# Placa_PCB_Robot_CAOS.net
KiCad netlist of a schematic drawn in EAGLE
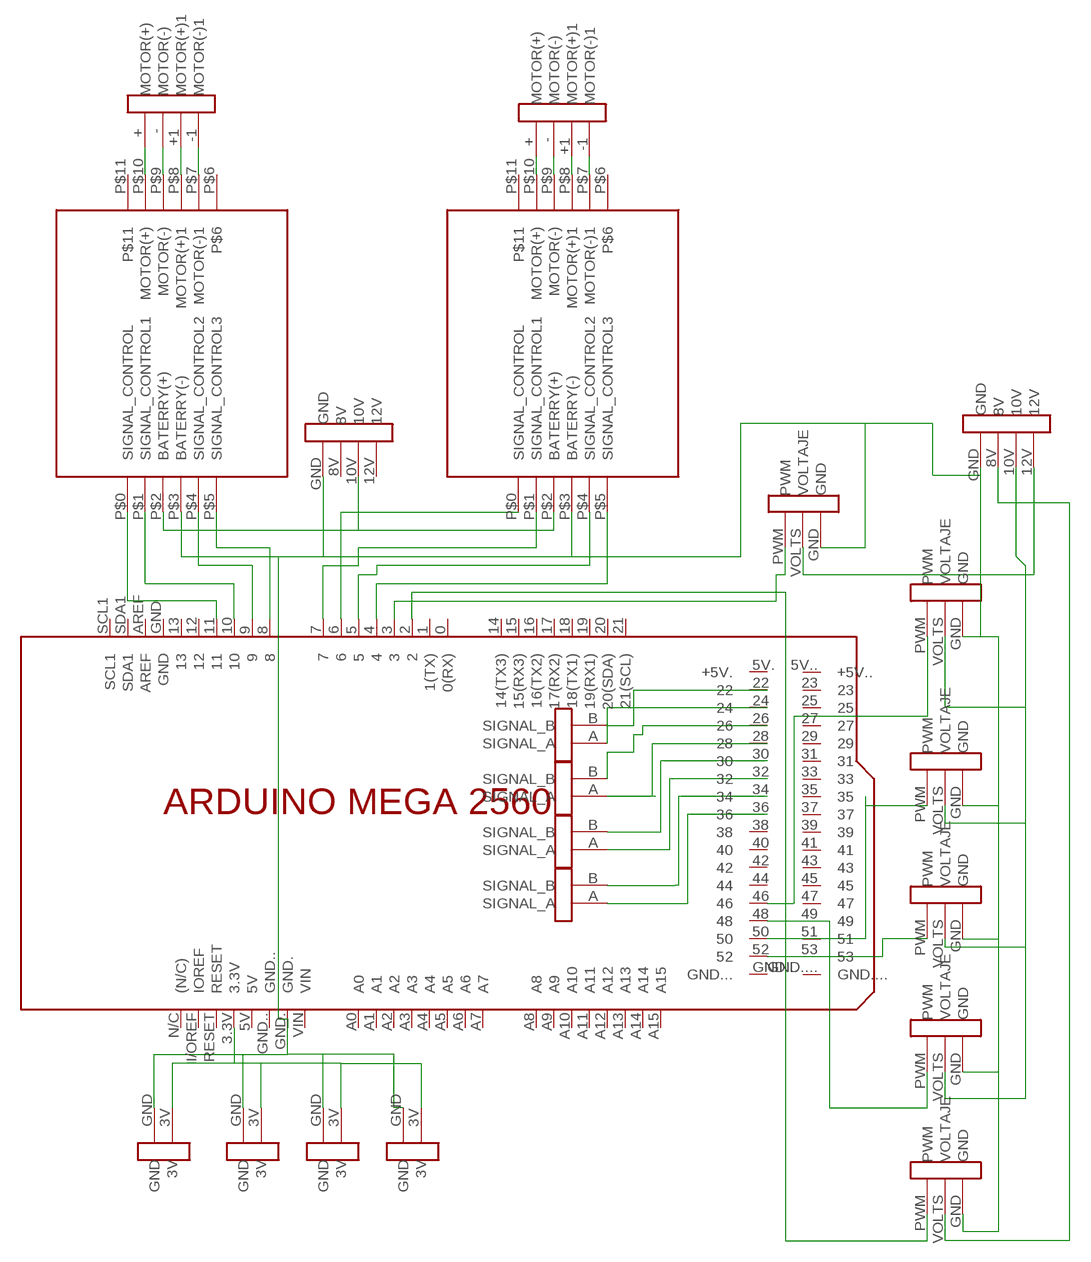
[diagram p0: schematic, sheet 1]

(export (version "E")
  (design (tool "Eeschema 10.0.6"))
  (components
    (comp (ref "INTENTO1")
      (value "DRV8833DRV8833")
      (footprint "eagle-import:DRV8833")
      (libsource (lib "eagle-import") (part "DRV8833DRV8833"))
    )
    (comp (ref "INTENTO2")
      (value "DRV8833DRV8833")
      (footprint "eagle-import:DRV8833")
      (libsource (lib "eagle-import") (part "DRV8833DRV8833"))
    )
    (comp (ref "PCB1")
      (value "ARDUINO_MEGA2560")
      (footprint "eagle-import:ARDUINO_MEGA2560")
      (libsource (lib "eagle-import") (part "ARDUINO_MEGA2560"))
    )
    (comp (ref "U$1")
      (value "MOTOR_CD")
      (footprint "eagle-import:MOTOR_CD")
      (libsource (lib "eagle-import") (part "MOTOR_CD"))
    )
    (comp (ref "U$2")
      (value "MOTOR_CD")
      (footprint "eagle-import:MOTOR_CD")
      (libsource (lib "eagle-import") (part "MOTOR_CD"))
    )
    (comp (ref "U$3")
      (value "BATTERY")
      (footprint "eagle-import:BATTERY")
      (libsource (lib "eagle-import") (part "BATTERY"))
    )
    (comp (ref "U$4")
      (value "SERVO_MOTORES")
      (footprint "eagle-import:SERVO_MOTOR")
      (libsource (lib "eagle-import") (part "SERVO_MOTORES"))
    )
    (comp (ref "U$5")
      (value "SERVO_MOTORES")
      (footprint "eagle-import:SERVO_MOTOR")
      (libsource (lib "eagle-import") (part "SERVO_MOTORES"))
    )
    (comp (ref "U$6")
      (value "SERVO_MOTORES")
      (footprint "eagle-import:SERVO_MOTOR")
      (libsource (lib "eagle-import") (part "SERVO_MOTORES"))
    )
    (comp (ref "U$7")
      (value "SERVO_MOTORES")
      (footprint "eagle-import:SERVO_MOTOR")
      (libsource (lib "eagle-import") (part "SERVO_MOTORES"))
    )
    (comp (ref "U$8")
      (value "SERVO_MOTORES")
      (footprint "eagle-import:SERVO_MOTOR")
      (libsource (lib "eagle-import") (part "SERVO_MOTORES"))
    )
    (comp (ref "U$9")
      (value "SERVO_MOTORES")
      (footprint "eagle-import:SERVO_MOTOR")
      (libsource (lib "eagle-import") (part "SERVO_MOTORES"))
    )
    (comp (ref "U$10")
      (value "BATTERY")
      (footprint "eagle-import:BATTERY")
      (libsource (lib "eagle-import") (part "BATTERY"))
    )
    (comp (ref "U$11")
      (value "ENCODER_VOLTAJE")
      (footprint "eagle-import:ENCODER_VOLTAJE")
      (libsource (lib "eagle-import") (part "ENCODER_VOLTAJE"))
    )
    (comp (ref "U$12")
      (value "ENCODER_VOLTAJE")
      (footprint "eagle-import:ENCODER_VOLTAJE")
      (libsource (lib "eagle-import") (part "ENCODER_VOLTAJE"))
    )
    (comp (ref "U$13")
      (value "ENCODER_VOLTAJE")
      (footprint "eagle-import:ENCODER_VOLTAJE")
      (libsource (lib "eagle-import") (part "ENCODER_VOLTAJE"))
    )
    (comp (ref "U$14")
      (value "ENCODER_VOLTAJE")
      (footprint "eagle-import:ENCODER_VOLTAJE")
      (libsource (lib "eagle-import") (part "ENCODER_VOLTAJE"))
    )
    (comp (ref "U$15")
      (value "SIGNAL_ENCODER2")
      (footprint "eagle-import:SIGNAL_ENCODER")
      (libsource (lib "eagle-import") (part "SIGNAL_ENCODER2"))
    )
    (comp (ref "U$16")
      (value "SIGNAL_ENCODER2")
      (footprint "eagle-import:SIGNAL_ENCODER")
      (libsource (lib "eagle-import") (part "SIGNAL_ENCODER2"))
    )
    (comp (ref "U$17")
      (value "SIGNAL_ENCODER2")
      (footprint "eagle-import:SIGNAL_ENCODER")
      (libsource (lib "eagle-import") (part "SIGNAL_ENCODER2"))
    )
    (comp (ref "U$18")
      (value "SIGNAL_ENCODER2")
      (footprint "eagle-import:SIGNAL_ENCODER")
      (libsource (lib "eagle-import") (part "SIGNAL_ENCODER2"))
    )
  )
  (nets
    (net (code "1") (name "Net-(INTENTO1-BATERRY(+))") (class "Default")
      (node (ref "INTENTO1") (pin "P$2") (pinfunction "BATERRY(+)_P$2") (pintype "bidirectional"))
      (node (ref "INTENTO2") (pin "P$2") (pinfunction "BATERRY(+)_P$2") (pintype "bidirectional"))
      (node (ref "U$3") (pin "10V") (pinfunction "10V_10V") (pintype "bidirectional"))
    )
    (net (code "2") (name "Net-(INTENTO1-BATERRY(-))") (class "Default")
      (node (ref "INTENTO1") (pin "P$3") (pinfunction "BATERRY(-)_P$3") (pintype "bidirectional"))
      (node (ref "INTENTO2") (pin "P$3") (pinfunction "BATERRY(-)_P$3") (pintype "bidirectional"))
      (node (ref "PCB1") (pin "GND.") (pinfunction "GND._GND.") (pintype "bidirectional"))
      (node (ref "U$10") (pin "GND") (pinfunction "GND_GND") (pintype "bidirectional"))
      (node (ref "U$11") (pin "GND") (pinfunction "GND_GND") (pintype "bidirectional"))
      (node (ref "U$12") (pin "GND") (pinfunction "GND_GND") (pintype "bidirectional"))
      (node (ref "U$13") (pin "GND") (pinfunction "GND_GND") (pintype "bidirectional"))
      (node (ref "U$14") (pin "GND") (pinfunction "GND_GND") (pintype "bidirectional"))
      (node (ref "U$3") (pin "GND") (pinfunction "GND_GND") (pintype "bidirectional"))
      (node (ref "U$4") (pin "GND") (pinfunction "GND_GND") (pintype "bidirectional"))
      (node (ref "U$5") (pin "GND") (pinfunction "GND_GND") (pintype "bidirectional"))
      (node (ref "U$6") (pin "GND") (pinfunction "GND_GND") (pintype "bidirectional"))
      (node (ref "U$7") (pin "GND") (pinfunction "GND_GND") (pintype "bidirectional"))
      (node (ref "U$8") (pin "GND") (pinfunction "GND_GND") (pintype "bidirectional"))
      (node (ref "U$9") (pin "GND") (pinfunction "GND_GND") (pintype "bidirectional"))
    )
    (net (code "3") (name "Net-(INTENTO1-MOTOR(+))") (class "Default")
      (node (ref "INTENTO1") (pin "P$10") (pinfunction "MOTOR(+)_P$10") (pintype "bidirectional"))
      (node (ref "U$1") (pin "+") (pinfunction "MOTOR(+)_+") (pintype "bidirectional"))
    )
    (net (code "4") (name "Net-(INTENTO1-MOTOR(+)1)") (class "Default")
      (node (ref "INTENTO1") (pin "P$8") (pinfunction "MOTOR(+)1_P$8") (pintype "bidirectional"))
      (node (ref "U$1") (pin "+1") (pinfunction "MOTOR(+)1_+1") (pintype "bidirectional"))
    )
    (net (code "5") (name "Net-(INTENTO1-MOTOR(-))") (class "Default")
      (node (ref "INTENTO1") (pin "P$9") (pinfunction "MOTOR(-)_P$9") (pintype "bidirectional"))
      (node (ref "U$1") (pin "-") (pinfunction "MOTOR(-)_-") (pintype "bidirectional"))
    )
    (net (code "6") (name "Net-(INTENTO1-MOTOR(-)1)") (class "Default")
      (node (ref "INTENTO1") (pin "P$7") (pinfunction "MOTOR(-)1_P$7") (pintype "bidirectional"))
      (node (ref "U$1") (pin "-1") (pinfunction "MOTOR(-)1_-1") (pintype "bidirectional"))
    )
    (net (code "7") (name "Net-(INTENTO1-SIGNAL_CONTROL)") (class "Default")
      (node (ref "INTENTO1") (pin "P$0") (pinfunction "SIGNAL_CONTROL_P$0") (pintype "bidirectional"))
      (node (ref "PCB1") (pin "11") (pinfunction "11_11") (pintype "bidirectional"))
    )
    (net (code "8") (name "Net-(INTENTO1-SIGNAL_CONTROL1)") (class "Default")
      (node (ref "INTENTO1") (pin "P$1") (pinfunction "SIGNAL_CONTROL1_P$1") (pintype "bidirectional"))
      (node (ref "PCB1") (pin "10") (pinfunction "10_10") (pintype "bidirectional"))
    )
    (net (code "9") (name "Net-(INTENTO1-SIGNAL_CONTROL2)") (class "Default")
      (node (ref "INTENTO1") (pin "P$4") (pinfunction "SIGNAL_CONTROL2_P$4") (pintype "bidirectional"))
      (node (ref "PCB1") (pin "9") (pinfunction "9_9") (pintype "bidirectional"))
    )
    (net (code "10") (name "Net-(INTENTO1-SIGNAL_CONTROL3)") (class "Default")
      (node (ref "INTENTO1") (pin "P$5") (pinfunction "SIGNAL_CONTROL3_P$5") (pintype "bidirectional"))
      (node (ref "PCB1") (pin "8") (pinfunction "8_8") (pintype "bidirectional"))
    )
    (net (code "11") (name "Net-(INTENTO2-MOTOR(+))") (class "Default")
      (node (ref "INTENTO2") (pin "P$10") (pinfunction "MOTOR(+)_P$10") (pintype "bidirectional"))
      (node (ref "U$2") (pin "+") (pinfunction "MOTOR(+)_+") (pintype "bidirectional"))
    )
    (net (code "12") (name "Net-(INTENTO2-MOTOR(+)1)") (class "Default")
      (node (ref "INTENTO2") (pin "P$8") (pinfunction "MOTOR(+)1_P$8") (pintype "bidirectional"))
      (node (ref "U$2") (pin "+1") (pinfunction "MOTOR(+)1_+1") (pintype "bidirectional"))
    )
    (net (code "13") (name "Net-(INTENTO2-MOTOR(-))") (class "Default")
      (node (ref "INTENTO2") (pin "P$9") (pinfunction "MOTOR(-)_P$9") (pintype "bidirectional"))
      (node (ref "U$2") (pin "-") (pinfunction "MOTOR(-)_-") (pintype "bidirectional"))
    )
    (net (code "14") (name "Net-(INTENTO2-MOTOR(-)1)") (class "Default")
      (node (ref "INTENTO2") (pin "P$7") (pinfunction "MOTOR(-)1_P$7") (pintype "bidirectional"))
      (node (ref "U$2") (pin "-1") (pinfunction "MOTOR(-)1_-1") (pintype "bidirectional"))
    )
    (net (code "15") (name "Net-(INTENTO2-SIGNAL_CONTROL)") (class "Default")
      (node (ref "INTENTO2") (pin "P$0") (pinfunction "SIGNAL_CONTROL_P$0") (pintype "bidirectional"))
      (node (ref "PCB1") (pin "6") (pinfunction "6_6") (pintype "bidirectional"))
    )
    (net (code "16") (name "Net-(INTENTO2-SIGNAL_CONTROL1)") (class "Default")
      (node (ref "INTENTO2") (pin "P$1") (pinfunction "SIGNAL_CONTROL1_P$1") (pintype "bidirectional"))
      (node (ref "PCB1") (pin "7") (pinfunction "7_7") (pintype "bidirectional"))
    )
    (net (code "17") (name "Net-(INTENTO2-SIGNAL_CONTROL2)") (class "Default")
      (node (ref "INTENTO2") (pin "P$4") (pinfunction "SIGNAL_CONTROL2_P$4") (pintype "bidirectional"))
      (node (ref "PCB1") (pin "5") (pinfunction "5_5") (pintype "bidirectional"))
    )
    (net (code "18") (name "Net-(INTENTO2-SIGNAL_CONTROL3)") (class "Default")
      (node (ref "INTENTO2") (pin "P$5") (pinfunction "SIGNAL_CONTROL3_P$5") (pintype "bidirectional"))
      (node (ref "PCB1") (pin "4") (pinfunction "4_4") (pintype "bidirectional"))
    )
    (net (code "19") (name "Net-(PCB1-Pad2)") (class "Default")
      (node (ref "PCB1") (pin "2") (pinfunction "2_2") (pintype "bidirectional"))
      (node (ref "U$9") (pin "PWM") (pinfunction "PWM_PWM") (pintype "bidirectional"))
    )
    (net (code "20") (name "Net-(PCB1-Pad3)") (class "Default")
      (node (ref "PCB1") (pin "3") (pinfunction "3_3") (pintype "bidirectional"))
      (node (ref "U$4") (pin "PWM") (pinfunction "PWM_PWM") (pintype "bidirectional"))
    )
    (net (code "21") (name "Net-(PCB1-Pad3.3V)") (class "Default")
      (node (ref "PCB1") (pin "3.3V") (pinfunction "3.3V_3.3V") (pintype "bidirectional"))
      (node (ref "U$11") (pin "3V") (pinfunction "3V_3V") (pintype "bidirectional"))
      (node (ref "U$12") (pin "3V") (pinfunction "3V_3V") (pintype "bidirectional"))
      (node (ref "U$13") (pin "3V") (pinfunction "3V_3V") (pintype "bidirectional"))
      (node (ref "U$14") (pin "3V") (pinfunction "3V_3V") (pintype "bidirectional"))
    )
    (net (code "22") (name "Net-(PCB1-Pad46)") (class "Default")
      (node (ref "PCB1") (pin "46") (pinfunction "46_46") (pintype "bidirectional"))
      (node (ref "U$5") (pin "PWM") (pinfunction "PWM_PWM") (pintype "bidirectional"))
    )
    (net (code "23") (name "Net-(PCB1-Pad48)") (class "Default")
      (node (ref "PCB1") (pin "48") (pinfunction "48_48") (pintype "bidirectional"))
      (node (ref "U$8") (pin "PWM") (pinfunction "PWM_PWM") (pintype "bidirectional"))
    )
    (net (code "24") (name "Net-(PCB1-Pad50)") (class "Default")
      (node (ref "PCB1") (pin "50") (pinfunction "50_50") (pintype "bidirectional"))
      (node (ref "U$6") (pin "PWM") (pinfunction "PWM_PWM") (pintype "bidirectional"))
    )
    (net (code "25") (name "Net-(PCB1-Pad52)") (class "Default")
      (node (ref "PCB1") (pin "52") (pinfunction "52_52") (pintype "bidirectional"))
      (node (ref "U$7") (pin "PWM") (pinfunction "PWM_PWM") (pintype "bidirectional"))
    )
    (net (code "26") (name "Net-(U$4-VOLTAJE)") (class "Default")
      (node (ref "U$10") (pin "12V") (pinfunction "12V_12V") (pintype "bidirectional"))
      (node (ref "U$4") (pin "VOLTS") (pinfunction "VOLTAJE_VOLTS") (pintype "bidirectional"))
    )
    (net (code "27") (name "Net-(U$5-VOLTAJE)") (class "Default")
      (node (ref "U$10") (pin "10V") (pinfunction "10V_10V") (pintype "bidirectional"))
      (node (ref "U$5") (pin "VOLTS") (pinfunction "VOLTAJE_VOLTS") (pintype "bidirectional"))
      (node (ref "U$6") (pin "VOLTS") (pinfunction "VOLTAJE_VOLTS") (pintype "bidirectional"))
      (node (ref "U$7") (pin "VOLTS") (pinfunction "VOLTAJE_VOLTS") (pintype "bidirectional"))
      (node (ref "U$8") (pin "VOLTS") (pinfunction "VOLTAJE_VOLTS") (pintype "bidirectional"))
    )
    (net (code "28") (name "Net-(U$9-VOLTAJE)") (class "Default")
      (node (ref "U$10") (pin "8V") (pinfunction "8V_8V") (pintype "bidirectional"))
      (node (ref "U$9") (pin "VOLTS") (pinfunction "VOLTAJE_VOLTS") (pintype "bidirectional"))
    )
    (net (code "29") (name "Net-(U$15-SIGNAL_A)") (class "Default")
      (node (ref "PCB1") (pin "24") (pinfunction "24_24") (pintype "bidirectional"))
      (node (ref "U$15") (pin "A") (pinfunction "SIGNAL_A_A") (pintype "bidirectional"))
    )
    (net (code "30") (name "Net-(U$15-SIGNAL_B)") (class "Default")
      (node (ref "PCB1") (pin "22") (pinfunction "22_22") (pintype "bidirectional"))
      (node (ref "U$15") (pin "B") (pinfunction "SIGNAL_B_B") (pintype "bidirectional"))
    )
    (net (code "31") (name "Net-(U$16-SIGNAL_A)") (class "Default")
      (node (ref "PCB1") (pin "28") (pinfunction "28_28") (pintype "bidirectional"))
      (node (ref "U$16") (pin "A") (pinfunction "SIGNAL_A_A") (pintype "bidirectional"))
    )
    (net (code "32") (name "Net-(U$16-SIGNAL_B)") (class "Default")
      (node (ref "PCB1") (pin "26") (pinfunction "26_26") (pintype "bidirectional"))
      (node (ref "U$16") (pin "B") (pinfunction "SIGNAL_B_B") (pintype "bidirectional"))
    )
    (net (code "33") (name "Net-(U$17-SIGNAL_A)") (class "Default")
      (node (ref "PCB1") (pin "32") (pinfunction "32_32") (pintype "bidirectional"))
      (node (ref "U$17") (pin "A") (pinfunction "SIGNAL_A_A") (pintype "bidirectional"))
    )
    (net (code "34") (name "Net-(U$17-SIGNAL_B)") (class "Default")
      (node (ref "PCB1") (pin "30") (pinfunction "30_30") (pintype "bidirectional"))
      (node (ref "U$17") (pin "B") (pinfunction "SIGNAL_B_B") (pintype "bidirectional"))
    )
    (net (code "35") (name "Net-(U$18-SIGNAL_A)") (class "Default")
      (node (ref "PCB1") (pin "36") (pinfunction "36_36") (pintype "bidirectional"))
      (node (ref "U$18") (pin "A") (pinfunction "SIGNAL_A_A") (pintype "bidirectional"))
    )
    (net (code "36") (name "Net-(U$18-SIGNAL_B)") (class "Default")
      (node (ref "PCB1") (pin "34") (pinfunction "34_34") (pintype "bidirectional"))
      (node (ref "U$18") (pin "B") (pinfunction "SIGNAL_B_B") (pintype "bidirectional"))
    )
    (net (code "37") (name "unconnected-(INTENTO1-PadP$6)") (class "Default")
      (node (ref "INTENTO1") (pin "P$6") (pinfunction "P$6_P$6") (pintype "bidirectional"))
    )
    (net (code "38") (name "unconnected-(INTENTO1-PadP$11)") (class "Default")
      (node (ref "INTENTO1") (pin "P$11") (pinfunction "P$11_P$11") (pintype "bidirectional"))
    )
    (net (code "39") (name "unconnected-(INTENTO2-PadP$6)") (class "Default")
      (node (ref "INTENTO2") (pin "P$6") (pinfunction "P$6_P$6") (pintype "bidirectional"))
    )
    (net (code "40") (name "unconnected-(INTENTO2-PadP$11)") (class "Default")
      (node (ref "INTENTO2") (pin "P$11") (pinfunction "P$11_P$11") (pintype "bidirectional"))
    )
    (net (code "41") (name "unconnected-(PCB1-(N{slash}C)-PadN{slash}C)") (class "Default")
      (node (ref "PCB1") (pin "N/C") (pinfunction "(N/C)_N/C") (pintype "bidirectional"))
    )
    (net (code "42") (name "unconnected-(PCB1-+5V.-Pad5V.)") (class "Default")
      (node (ref "PCB1") (pin "5V.") (pinfunction "+5V._5V.") (pintype "bidirectional"))
    )
    (net (code "43") (name "unconnected-(PCB1-+5V..-Pad5V..)") (class "Default")
      (node (ref "PCB1") (pin "5V..") (pinfunction "+5V.._5V..") (pintype "bidirectional"))
    )
    (net (code "44") (name "unconnected-(PCB1-0(RX)-Pad0)") (class "Default")
      (node (ref "PCB1") (pin "0") (pinfunction "0(RX)_0") (pintype "bidirectional"))
    )
    (net (code "45") (name "unconnected-(PCB1-1(TX)-Pad1)") (class "Default")
      (node (ref "PCB1") (pin "1") (pinfunction "1(TX)_1") (pintype "bidirectional"))
    )
    (net (code "46") (name "unconnected-(PCB1-14(TX3)-Pad14)") (class "Default")
      (node (ref "PCB1") (pin "14") (pinfunction "14(TX3)_14") (pintype "bidirectional"))
    )
    (net (code "47") (name "unconnected-(PCB1-15(RX3)-Pad15)") (class "Default")
      (node (ref "PCB1") (pin "15") (pinfunction "15(RX3)_15") (pintype "bidirectional"))
    )
    (net (code "48") (name "unconnected-(PCB1-16(TX2)-Pad16)") (class "Default")
      (node (ref "PCB1") (pin "16") (pinfunction "16(TX2)_16") (pintype "bidirectional"))
    )
    (net (code "49") (name "unconnected-(PCB1-17(RX2)-Pad17)") (class "Default")
      (node (ref "PCB1") (pin "17") (pinfunction "17(RX2)_17") (pintype "bidirectional"))
    )
    (net (code "50") (name "unconnected-(PCB1-18(TX1)-Pad18)") (class "Default")
      (node (ref "PCB1") (pin "18") (pinfunction "18(TX1)_18") (pintype "bidirectional"))
    )
    (net (code "51") (name "unconnected-(PCB1-19(RX1)-Pad19)") (class "Default")
      (node (ref "PCB1") (pin "19") (pinfunction "19(RX1)_19") (pintype "bidirectional"))
    )
    (net (code "52") (name "unconnected-(PCB1-20(SDA)-Pad20)") (class "Default")
      (node (ref "PCB1") (pin "20") (pinfunction "20(SDA)_20") (pintype "bidirectional"))
    )
    (net (code "53") (name "unconnected-(PCB1-21(SCL)-Pad21)") (class "Default")
      (node (ref "PCB1") (pin "21") (pinfunction "21(SCL)_21") (pintype "bidirectional"))
    )
    (net (code "54") (name "unconnected-(PCB1-IOREF-PadI{slash}OREF)") (class "Default")
      (node (ref "PCB1") (pin "I/OREF") (pinfunction "IOREF_I/OREF") (pintype "bidirectional"))
    )
    (net (code "55") (name "unconnected-(PCB1-Pad5V)") (class "Default")
      (node (ref "PCB1") (pin "5V") (pinfunction "5V_5V") (pintype "bidirectional"))
    )
    (net (code "56") (name "unconnected-(PCB1-Pad12)") (class "Default")
      (node (ref "PCB1") (pin "12") (pinfunction "12_12") (pintype "bidirectional"))
    )
    (net (code "57") (name "unconnected-(PCB1-Pad13)") (class "Default")
      (node (ref "PCB1") (pin "13") (pinfunction "13_13") (pintype "bidirectional"))
    )
    (net (code "58") (name "unconnected-(PCB1-Pad23)") (class "Default")
      (node (ref "PCB1") (pin "23") (pinfunction "23_23") (pintype "bidirectional"))
    )
    (net (code "59") (name "unconnected-(PCB1-Pad25)") (class "Default")
      (node (ref "PCB1") (pin "25") (pinfunction "25_25") (pintype "bidirectional"))
    )
    (net (code "60") (name "unconnected-(PCB1-Pad27)") (class "Default")
      (node (ref "PCB1") (pin "27") (pinfunction "27_27") (pintype "bidirectional"))
    )
    (net (code "61") (name "unconnected-(PCB1-Pad29)") (class "Default")
      (node (ref "PCB1") (pin "29") (pinfunction "29_29") (pintype "bidirectional"))
    )
    (net (code "62") (name "unconnected-(PCB1-Pad31)") (class "Default")
      (node (ref "PCB1") (pin "31") (pinfunction "31_31") (pintype "bidirectional"))
    )
    (net (code "63") (name "unconnected-(PCB1-Pad33)") (class "Default")
      (node (ref "PCB1") (pin "33") (pinfunction "33_33") (pintype "bidirectional"))
    )
    (net (code "64") (name "unconnected-(PCB1-Pad35)") (class "Default")
      (node (ref "PCB1") (pin "35") (pinfunction "35_35") (pintype "bidirectional"))
    )
    (net (code "65") (name "unconnected-(PCB1-Pad37)") (class "Default")
      (node (ref "PCB1") (pin "37") (pinfunction "37_37") (pintype "bidirectional"))
    )
    (net (code "66") (name "unconnected-(PCB1-Pad38)") (class "Default")
      (node (ref "PCB1") (pin "38") (pinfunction "38_38") (pintype "bidirectional"))
    )
    (net (code "67") (name "unconnected-(PCB1-Pad39)") (class "Default")
      (node (ref "PCB1") (pin "39") (pinfunction "39_39") (pintype "bidirectional"))
    )
    (net (code "68") (name "unconnected-(PCB1-Pad40)") (class "Default")
      (node (ref "PCB1") (pin "40") (pinfunction "40_40") (pintype "bidirectional"))
    )
    (net (code "69") (name "unconnected-(PCB1-Pad41)") (class "Default")
      (node (ref "PCB1") (pin "41") (pinfunction "41_41") (pintype "bidirectional"))
    )
    (net (code "70") (name "unconnected-(PCB1-Pad42)") (class "Default")
      (node (ref "PCB1") (pin "42") (pinfunction "42_42") (pintype "bidirectional"))
    )
    (net (code "71") (name "unconnected-(PCB1-Pad43)") (class "Default")
      (node (ref "PCB1") (pin "43") (pinfunction "43_43") (pintype "bidirectional"))
    )
    (net (code "72") (name "unconnected-(PCB1-Pad44)") (class "Default")
      (node (ref "PCB1") (pin "44") (pinfunction "44_44") (pintype "bidirectional"))
    )
    (net (code "73") (name "unconnected-(PCB1-Pad45)") (class "Default")
      (node (ref "PCB1") (pin "45") (pinfunction "45_45") (pintype "bidirectional"))
    )
    (net (code "74") (name "unconnected-(PCB1-Pad47)") (class "Default")
      (node (ref "PCB1") (pin "47") (pinfunction "47_47") (pintype "bidirectional"))
    )
    (net (code "75") (name "unconnected-(PCB1-Pad49)") (class "Default")
      (node (ref "PCB1") (pin "49") (pinfunction "49_49") (pintype "bidirectional"))
    )
    (net (code "76") (name "unconnected-(PCB1-Pad51)") (class "Default")
      (node (ref "PCB1") (pin "51") (pinfunction "51_51") (pintype "bidirectional"))
    )
    (net (code "77") (name "unconnected-(PCB1-Pad53)") (class "Default")
      (node (ref "PCB1") (pin "53") (pinfunction "53_53") (pintype "bidirectional"))
    )
    (net (code "78") (name "unconnected-(PCB1-PadA0)") (class "Default")
      (node (ref "PCB1") (pin "A0") (pinfunction "A0_A0") (pintype "bidirectional"))
    )
    (net (code "79") (name "unconnected-(PCB1-PadA1)") (class "Default")
      (node (ref "PCB1") (pin "A1") (pinfunction "A1_A1") (pintype "bidirectional"))
    )
    (net (code "80") (name "unconnected-(PCB1-PadA2)") (class "Default")
      (node (ref "PCB1") (pin "A2") (pinfunction "A2_A2") (pintype "bidirectional"))
    )
    (net (code "81") (name "unconnected-(PCB1-PadA3)") (class "Default")
      (node (ref "PCB1") (pin "A3") (pinfunction "A3_A3") (pintype "bidirectional"))
    )
    (net (code "82") (name "unconnected-(PCB1-PadA4)") (class "Default")
      (node (ref "PCB1") (pin "A4") (pinfunction "A4_A4") (pintype "bidirectional"))
    )
    (net (code "83") (name "unconnected-(PCB1-PadA5)") (class "Default")
      (node (ref "PCB1") (pin "A5") (pinfunction "A5_A5") (pintype "bidirectional"))
    )
    (net (code "84") (name "unconnected-(PCB1-PadA6)") (class "Default")
      (node (ref "PCB1") (pin "A6") (pinfunction "A6_A6") (pintype "bidirectional"))
    )
    (net (code "85") (name "unconnected-(PCB1-PadA7)") (class "Default")
      (node (ref "PCB1") (pin "A7") (pinfunction "A7_A7") (pintype "bidirectional"))
    )
    (net (code "86") (name "unconnected-(PCB1-PadA8)") (class "Default")
      (node (ref "PCB1") (pin "A8") (pinfunction "A8_A8") (pintype "bidirectional"))
    )
    (net (code "87") (name "unconnected-(PCB1-PadA9)") (class "Default")
      (node (ref "PCB1") (pin "A9") (pinfunction "A9_A9") (pintype "bidirectional"))
    )
    (net (code "88") (name "unconnected-(PCB1-PadA10)") (class "Default")
      (node (ref "PCB1") (pin "A10") (pinfunction "A10_A10") (pintype "bidirectional"))
    )
    (net (code "89") (name "unconnected-(PCB1-PadA11)") (class "Default")
      (node (ref "PCB1") (pin "A11") (pinfunction "A11_A11") (pintype "bidirectional"))
    )
    (net (code "90") (name "unconnected-(PCB1-PadA12)") (class "Default")
      (node (ref "PCB1") (pin "A12") (pinfunction "A12_A12") (pintype "bidirectional"))
    )
    (net (code "91") (name "unconnected-(PCB1-PadA13)") (class "Default")
      (node (ref "PCB1") (pin "A13") (pinfunction "A13_A13") (pintype "bidirectional"))
    )
    (net (code "92") (name "unconnected-(PCB1-PadA14)") (class "Default")
      (node (ref "PCB1") (pin "A14") (pinfunction "A14_A14") (pintype "bidirectional"))
    )
    (net (code "93") (name "unconnected-(PCB1-PadA15)") (class "Default")
      (node (ref "PCB1") (pin "A15") (pinfunction "A15_A15") (pintype "bidirectional"))
    )
    (net (code "94") (name "unconnected-(PCB1-PadAREF)") (class "Default")
      (node (ref "PCB1") (pin "AREF") (pinfunction "AREF_AREF") (pintype "bidirectional"))
    )
    (net (code "95") (name "unconnected-(PCB1-PadGND)") (class "Default")
      (node (ref "PCB1") (pin "GND") (pinfunction "GND_GND") (pintype "bidirectional"))
    )
    (net (code "96") (name "unconnected-(PCB1-PadGND..)") (class "Default")
      (node (ref "PCB1") (pin "GND..") (pinfunction "GND.._GND..") (pintype "bidirectional"))
    )
    (net (code "97") (name "unconnected-(PCB1-PadGND...)") (class "Default")
      (node (ref "PCB1") (pin "GND...") (pinfunction "GND..._GND...") (pintype "bidirectional"))
    )
    (net (code "98") (name "unconnected-(PCB1-PadGND....)") (class "Default")
      (node (ref "PCB1") (pin "GND....") (pinfunction "GND...._GND....") (pintype "bidirectional"))
    )
    (net (code "99") (name "unconnected-(PCB1-PadRESET)") (class "Default")
      (node (ref "PCB1") (pin "RESET") (pinfunction "RESET_RESET") (pintype "bidirectional"))
    )
    (net (code "100") (name "unconnected-(PCB1-PadSCL1)") (class "Default")
      (node (ref "PCB1") (pin "SCL1") (pinfunction "SCL1_SCL1") (pintype "bidirectional"))
    )
    (net (code "101") (name "unconnected-(PCB1-PadSDA1)") (class "Default")
      (node (ref "PCB1") (pin "SDA1") (pinfunction "SDA1_SDA1") (pintype "bidirectional"))
    )
    (net (code "102") (name "unconnected-(PCB1-PadVIN)") (class "Default")
      (node (ref "PCB1") (pin "VIN") (pinfunction "VIN_VIN") (pintype "bidirectional"))
    )
    (net (code "103") (name "unconnected-(U$3-Pad8V)") (class "Default")
      (node (ref "U$3") (pin "8V") (pinfunction "8V_8V") (pintype "bidirectional"))
    )
    (net (code "104") (name "unconnected-(U$3-Pad12V)") (class "Default")
      (node (ref "U$3") (pin "12V") (pinfunction "12V_12V") (pintype "bidirectional"))
    )
  )
)
